# Sheet1.net
KiCad netlist of a schematic drawn in Altium Designer
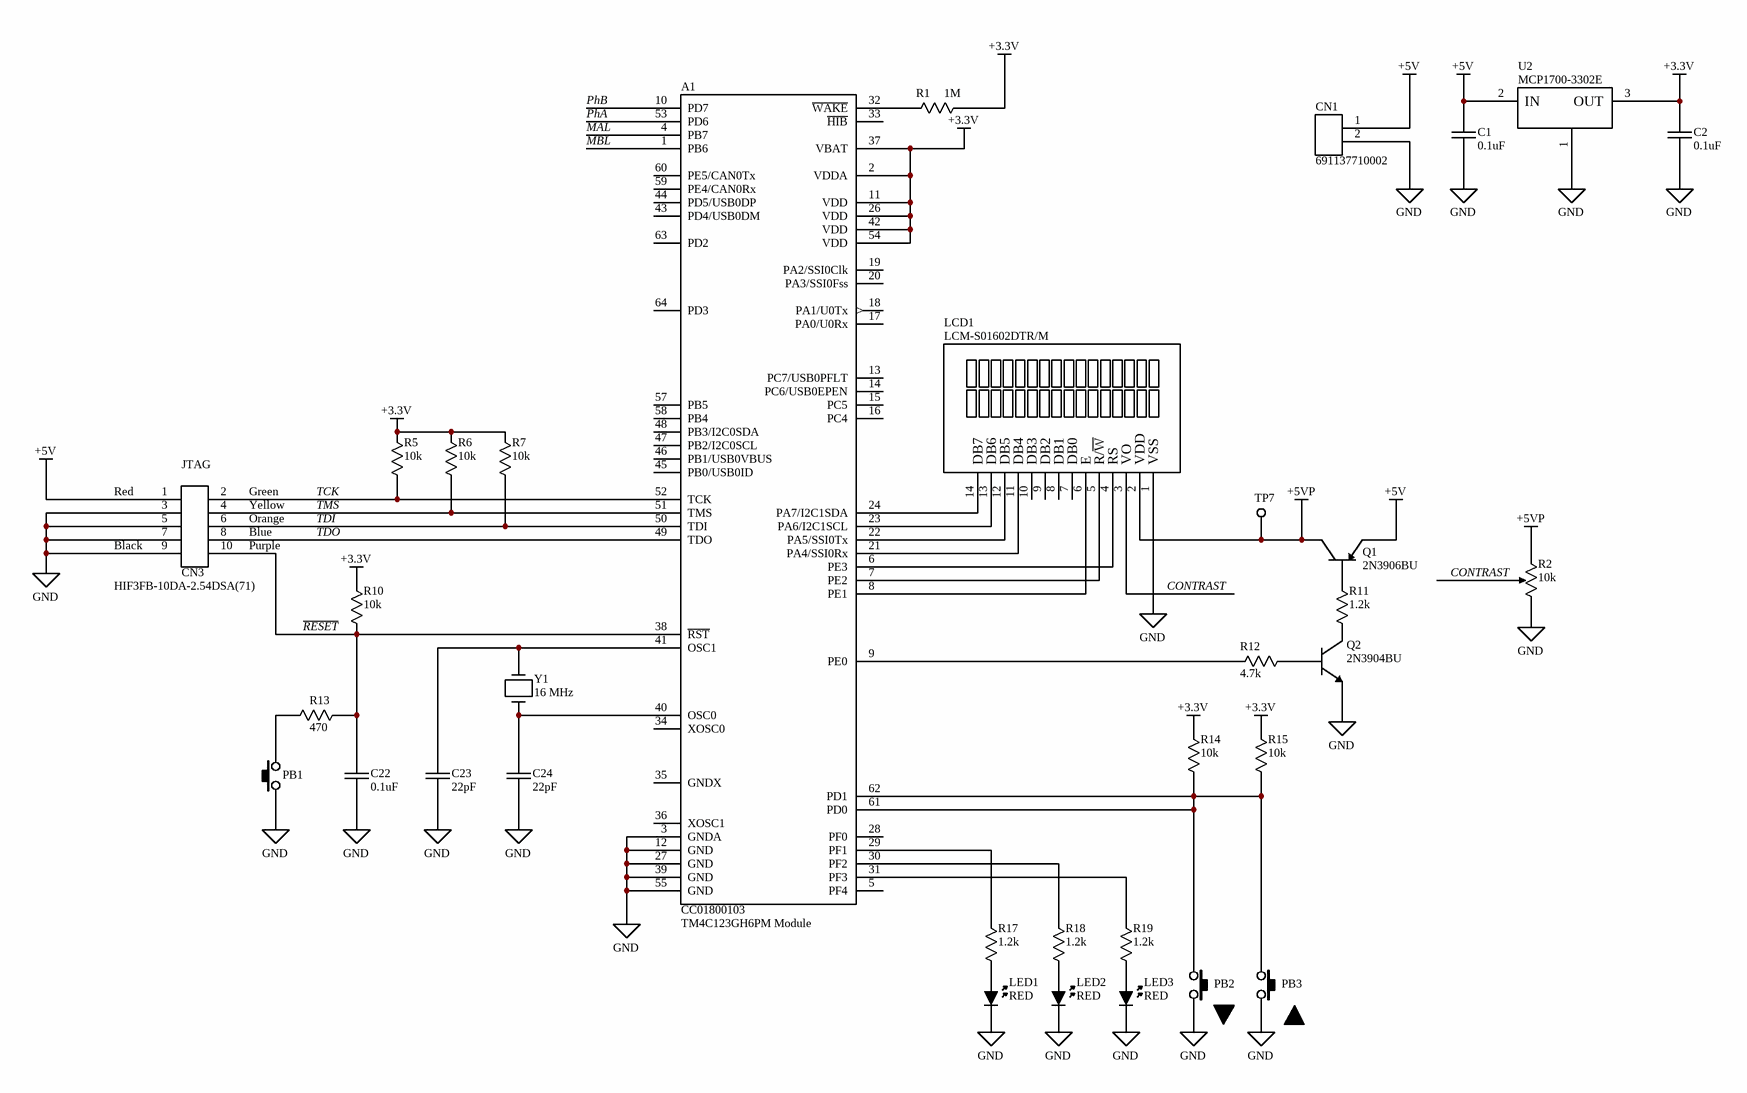
[diagram p0: Sheet1.SchDoc]

(export (version "E")
  (design (tool "Eeschema 10.0.6"))
  (components
    (comp (ref "A1")
      (value "CC01800103")
      (footprint "CC01800102")
      (description "Tiva TM4C123GH6PM Microcontroller Module")
      (fields
        (field (name "MANUFACTURER") "Confederation College")
        (field (name "MICROCONTROLLER") "TM4C123GH6PM Module")
      )
      (libsource (lib "Schlib1") (part "CC01800103"))
    )
    (comp (ref "C1")
      (value "0.1uF")
      (footprint "C320C104M5R5TA")
      (description "0.1 uF, 50 V Ceramic Capacitor")
      (fields (field (name "MANUFACTURER") "Kemet") (field (name "PARTNUMBER") "C320C104M5R5TA"))
      (libsource (lib "Schlib1") (part "C320C104M5R5TA"))
    )
    (comp (ref "C2")
      (value "0.1uF")
      (footprint "C320C104M5R5TA")
      (description "0.1 uF, 50 V Ceramic Capacitor")
      (fields (field (name "MANUFACTURER") "Kemet") (field (name "PARTNUMBER") "C320C104M5R5TA"))
      (libsource (lib "Schlib1") (part "C320C104M5R5TA"))
    )
    (comp (ref "C22")
      (value "0.1uF")
      (footprint "C320C104M5R5TA")
      (description "0.1 uF, 50 V Ceramic Capacitor")
      (fields (field (name "MANUFACTURER") "Kemet") (field (name "PARTNUMBER") "C320C104M5R5TA"))
      (libsource (lib "Schlib1") (part "C320C104M5R5TA"))
    )
    (comp (ref "C23")
      (value "22pF")
      (footprint "K220J15C0GF5TH5")
      (description "22 pF, 50 V Ceramic Capacitor")
      (fields (field (name "MANUFACTURER") "Vishay") (field (name "PARTNUMBER") "K220J15C0GF5TH5"))
      (libsource (lib "Schlib1") (part "K220J15C0GF5TH5"))
    )
    (comp (ref "C24")
      (value "22pF")
      (footprint "K220J15C0GF5TH5")
      (description "22 pF, 50 V Ceramic Capacitor")
      (fields (field (name "MANUFACTURER") "Vishay") (field (name "PARTNUMBER") "K220J15C0GF5TH5"))
      (libsource (lib "Schlib1") (part "K220J15C0GF5TH5"))
    )
    (comp (ref "CN1")
      (value "691137710002")
      (footprint "691137710002")
      (description "TERM BLK 2POS SIDE ENTRY 5MM PCB")
      (fields (field (name "MANUFACTURER") "Wurth Elektronk"))
      (libsource (lib "Schlib1") (part "691137710002"))
    )
    (comp (ref "CN3")
      (value "HIF3FB-10DA-2.54DSA(71)")
      (footprint "HIF3FB-10DA-2.54DSA(71)")
      (description "CONN RCPT 10POS 0.1 GOLD PCB")
      (fields (field (name "MANUFACTURER") "Hirose Electric Co, Ltd"))
      (libsource (lib "Schlib1") (part "HIF3FB-10DA-2.54DSA(71)"))
    )
    (comp (ref "LCD1")
      (value "LCM-S01602DTR/M")
      (footprint "LCM-S01602DTR/M")
      (description "16x2 Character LCD Module, TN, Reflective")
      (fields (field (name "MANUFACTURER") "Lumex, Inc."))
      (libsource (lib "Schlib1") (part "LCM-S01602DTR/M"))
    )
    (comp (ref "LED1")
      (value "RED")
      (footprint "C503B-RCN-CW0Z0AA1")
      (description "5 mm Red Round LED")
      (fields (field (name "MANUFACTURER") "Cree, Inc.") (field (name "PARTNUMBER") "C503B-RCN-CW0Z0AA1"))
      (libsource (lib "Schlib1") (part "C503B-RCN-CW0Z0AA1"))
    )
    (comp (ref "LED2")
      (value "RED")
      (footprint "C503B-RCN-CW0Z0AA1")
      (description "5 mm Red Round LED")
      (fields (field (name "MANUFACTURER") "Cree, Inc.") (field (name "PARTNUMBER") "C503B-RCN-CW0Z0AA1"))
      (libsource (lib "Schlib1") (part "C503B-RCN-CW0Z0AA1"))
    )
    (comp (ref "LED3")
      (value "RED")
      (footprint "C503B-RCN-CW0Z0AA1")
      (description "5 mm Red Round LED")
      (fields (field (name "MANUFACTURER") "Cree, Inc.") (field (name "PARTNUMBER") "C503B-RCN-CW0Z0AA1"))
      (libsource (lib "Schlib1") (part "C503B-RCN-CW0Z0AA1"))
    )
    (comp (ref "PB1")
      (value "3-1825910-5")
      (footprint "3-1825910-5")
      (description "SWITCH TACTILE SPST-NO 0.05A 24V")
      (fields (field (name "MANUFACTURER") "TE Connectivity ALCOSWITCH Switches"))
      (libsource (lib "") (part "3-1825910-5_1"))
    )
    (comp (ref "PB2")
      (value "3-1825910-5")
      (footprint "3-1825910-5")
      (description "SWITCH TACTILE SPST-NO 0.05A 24V")
      (fields (field (name "MANUFACTURER") "TE Connectivity ALCOSWITCH Switches"))
      (libsource (lib "Schlib1") (part "3-1825910-5"))
    )
    (comp (ref "PB3")
      (value "3-1825910-5")
      (footprint "3-1825910-5")
      (description "SWITCH TACTILE SPST-NO 0.05A 24V")
      (fields (field (name "MANUFACTURER") "TE Connectivity ALCOSWITCH Switches"))
      (libsource (lib "Schlib1") (part "3-1825910-5"))
    )
    (comp (ref "Q1")
      (value "2N3906BU")
      (footprint "2N3906BU")
      (description "PNP General Purpose Amplifier")
      (fields (field (name "MANUFACTURER") "Fairchild Semiconductor Corporation"))
      (libsource (lib "Schlib1") (part "2N3906BU"))
    )
    (comp (ref "Q2")
      (value "2N3904BU")
      (footprint "2N3904BU")
      (description "NPN General Purpose Amplifier")
      (fields (field (name "MANUFACTURER") "Fairchild Semiconductor Corporation"))
      (libsource (lib "Schlib1") (part "2N3904BU"))
    )
    (comp (ref "R1")
      (value "1M")
      (footprint "1/2WattResistor")
      (description "1 Mega Ohm, ±5%, 0.5W Thru-Hole Resistor")
      (fields (field (name "MANUFACTURER") "Generic") (field (name "PARTNUMBER") "RES1k2-500mW-THRU-HOLE"))
      (libsource (lib "Schlib1") (part "RES1M-500mW-THRU-HOLE"))
    )
    (comp (ref "R2")
      (value "10k")
      (footprint "T93YA103KT20")
      (description "10 k, 21-Turn Trimmer")
      (fields (field (name "MANUFACTURER") "Vishay Sfernice") (field (name "PARTNUMBER") "T93YA103KT20"))
      (libsource (lib "Schlib1") (part "T93YA103KT20"))
    )
    (comp (ref "R5")
      (value "10k")
      (footprint "1/2WattResistor")
      (description "10k, ±5%, 0.5W Thru-Hole Resistor")
      (fields (field (name "MANUFACTURER") "Generic") (field (name "PARTNUMBER") "RES10k-500mW-THRU-HOLE"))
      (libsource (lib "Schlib1") (part "RES10k-500mW-THRU-HOLE"))
    )
    (comp (ref "R6")
      (value "10k")
      (footprint "1/2WattResistor")
      (description "10k, ±5%, 0.5W Thru-Hole Resistor")
      (fields (field (name "MANUFACTURER") "Generic") (field (name "PARTNUMBER") "RES10k-500mW-THRU-HOLE"))
      (libsource (lib "Schlib1") (part "RES10k-500mW-THRU-HOLE"))
    )
    (comp (ref "R7")
      (value "10k")
      (footprint "1/2WattResistor")
      (description "10k, ±5%, 0.5W Thru-Hole Resistor")
      (fields (field (name "MANUFACTURER") "Generic") (field (name "PARTNUMBER") "RES10k-500mW-THRU-HOLE"))
      (libsource (lib "Schlib1") (part "RES10k-500mW-THRU-HOLE"))
    )
    (comp (ref "R10")
      (value "10k")
      (footprint "1/2WattResistor")
      (description "10k, ±5%, 0.5W Thru-Hole Resistor")
      (fields (field (name "MANUFACTURER") "Generic") (field (name "PARTNUMBER") "RES10k-500mW-THRU-HOLE"))
      (libsource (lib "Schlib1") (part "RES10k-500mW-THRU-HOLE"))
    )
    (comp (ref "R11")
      (value "1.2k")
      (footprint "1/2WattResistor")
      (description "1.2k, ±5%, 0.5W Thru-Hole Resistor")
      (fields (field (name "MANUFACTURER") "Generic") (field (name "PARTNUMBER") "RES1k2-500mW-THRU-HOLE"))
      (libsource (lib "Schlib1") (part "RES1k2-500mW-THRU-HOLE"))
    )
    (comp (ref "R12")
      (value "4.7k")
      (footprint "1/2WattResistor")
      (description "4.7 kOhm, ±5%, 0.5W Thru-Hole Resistor")
      (fields (field (name "MANUFACTURER") "Generic") (field (name "PARTNUMBER") "RES4k7-500mW-THRU-HOLE"))
      (libsource (lib "Schlib1") (part "RES4k7-500mW-THRU-HOLE"))
    )
    (comp (ref "R13")
      (value "470")
      (footprint "1/2WattResistor")
      (description "470 Ohm, ±5%, 0.5W Thru-Hole Resistor")
      (fields (field (name "MANUFACTURER") "Generic") (field (name "PARTNUMBER") "RES470-500mW-THRU-HOLE"))
      (libsource (lib "Schlib1") (part "RES470-500mW-THRU-HOLE"))
    )
    (comp (ref "R14")
      (value "10k")
      (footprint "1/2WattResistor")
      (description "10k, ±5%, 0.5W Thru-Hole Resistor")
      (fields (field (name "MANUFACTURER") "Generic") (field (name "PARTNUMBER") "RES10k-500mW-THRU-HOLE"))
      (libsource (lib "Schlib1") (part "RES10k-500mW-THRU-HOLE"))
    )
    (comp (ref "R15")
      (value "10k")
      (footprint "1/2WattResistor")
      (description "10k, ±5%, 0.5W Thru-Hole Resistor")
      (fields (field (name "MANUFACTURER") "Generic") (field (name "PARTNUMBER") "RES10k-500mW-THRU-HOLE"))
      (libsource (lib "Schlib1") (part "RES10k-500mW-THRU-HOLE"))
    )
    (comp (ref "R17")
      (value "1.2k")
      (footprint "1/2WattResistor")
      (description "1.2k, ±5%, 0.5W Thru-Hole Resistor")
      (fields (field (name "MANUFACTURER") "Generic") (field (name "PARTNUMBER") "RES1k2-500mW-THRU-HOLE"))
      (libsource (lib "Schlib1") (part "RES1k2-500mW-THRU-HOLE"))
    )
    (comp (ref "R18")
      (value "1.2k")
      (footprint "1/2WattResistor")
      (description "1.2k, ±5%, 0.5W Thru-Hole Resistor")
      (fields (field (name "MANUFACTURER") "Generic") (field (name "PARTNUMBER") "RES1k2-500mW-THRU-HOLE"))
      (libsource (lib "Schlib1") (part "RES1k2-500mW-THRU-HOLE"))
    )
    (comp (ref "R19")
      (value "1.2k")
      (footprint "1/2WattResistor")
      (description "1.2k, ±5%, 0.5W Thru-Hole Resistor")
      (fields (field (name "MANUFACTURER") "Generic") (field (name "PARTNUMBER") "RES1k2-500mW-THRU-HOLE"))
      (libsource (lib "Schlib1") (part "RES1k2-500mW-THRU-HOLE"))
    )
    (comp (ref "TP7")
      (value "TESTPOINT-2MM")
      (footprint "TESTPOINT-2MM")
      (description "Test Point 2MM diameter")
      (libsource (lib "Schlib1") (part "TESTPOINT-2MM"))
    )
    (comp (ref "U2")
      (value "MCP1700-3302E")
      (footprint "MCP1700-3302E/TO")
      (description "Low Quiescent Current LDO")
      (fields (field (name "MANUFACTURER") "Microchip Technology"))
      (libsource (lib "Schlib1") (part "MCP1700-3302E"))
    )
    (comp (ref "Y1")
      (value "16 MHz")
      (footprint "ABL-16.000MHZ-B2")
      (description "16 MHz AC/49US (AT49) Microprocessor Crystall")
      (fields
        (field (name "PARTNUMBER") "ABL-16.000MHZ-B2")
        (field (name "MANUFACTURER") "Abracon Corporation")
      )
      (libsource (lib "Schlib1") (part "ABL-16.000MHZ-B2"))
    )
  )
  (nets
    (net (code "1") (name "+3.3V") (class "Default")
      (node (ref "A1") (pin "11") (pinfunction "VDD_11") (pintype "power_in"))
      (node (ref "A1") (pin "2") (pinfunction "VDDA_2") (pintype "power_in"))
      (node (ref "A1") (pin "26") (pinfunction "VDD_26") (pintype "passive"))
      (node (ref "A1") (pin "37") (pinfunction "VBAT_37") (pintype "passive"))
      (node (ref "A1") (pin "42") (pinfunction "VDD_42") (pintype "passive"))
      (node (ref "A1") (pin "54") (pinfunction "VDD_54") (pintype "power_in"))
      (node (ref "C2") (pin "2") (pinfunction "2_2") (pintype "passive"))
      (node (ref "R1") (pin "2") (pinfunction "2_2") (pintype "passive"))
      (node (ref "R10") (pin "2") (pinfunction "2_2") (pintype "passive"))
      (node (ref "R14") (pin "2") (pinfunction "2_2") (pintype "passive"))
      (node (ref "R15") (pin "2") (pinfunction "2_2") (pintype "passive"))
      (node (ref "R5") (pin "2") (pinfunction "2_2") (pintype "passive"))
      (node (ref "R6") (pin "2") (pinfunction "2_2") (pintype "passive"))
      (node (ref "R7") (pin "2") (pinfunction "2_2") (pintype "passive"))
      (node (ref "U2") (pin "3") (pinfunction "OUT_3") (pintype "passive"))
    )
    (net (code "2") (name "+5V") (class "Default")
      (node (ref "C1") (pin "2") (pinfunction "2_2") (pintype "passive"))
      (node (ref "CN1") (pin "1") (pinfunction "1_1") (pintype "passive"))
      (node (ref "CN3") (pin "1") (pinfunction "1_1") (pintype "passive"))
      (node (ref "Q1") (pin "1") (pinfunction "E_1") (pintype "passive"))
      (node (ref "U2") (pin "2") (pinfunction "IN_2") (pintype "passive"))
    )
    (net (code "3") (name "+5VP") (class "Default")
      (node (ref "LCD1") (pin "2") (pinfunction "VDD_2") (pintype "passive"))
      (node (ref "Q1") (pin "3") (pinfunction "C_3") (pintype "passive"))
      (node (ref "R2") (pin "1") (pinfunction "1_1") (pintype "passive"))
      (node (ref "TP7") (pin "1") (pintype "passive"))
    )
    (net (code "4") (name "/CONTRAST") (class "Default")
      (node (ref "LCD1") (pin "3") (pinfunction "VO_3") (pintype "passive"))
      (node (ref "R2") (pin "2") (pinfunction "2_2") (pintype "passive"))
    )
    (net (code "5") (name "/MAL") (class "Default")
      (node (ref "A1") (pin "4") (pinfunction "PB7_4") (pintype "passive"))
    )
    (net (code "6") (name "/MBL") (class "Default")
      (node (ref "A1") (pin "1") (pinfunction "PB6_1") (pintype "passive"))
    )
    (net (code "7") (name "/PhA") (class "Default")
      (node (ref "A1") (pin "53") (pinfunction "PD6_53") (pintype "passive"))
    )
    (net (code "8") (name "/PhB") (class "Default")
      (node (ref "A1") (pin "10") (pinfunction "PD7_10") (pintype "passive"))
    )
    (net (code "9") (name "/TCK") (class "Default")
      (node (ref "A1") (pin "52") (pinfunction "TCK_52") (pintype "passive"))
      (node (ref "CN3") (pin "2") (pinfunction "2_2") (pintype "passive"))
      (node (ref "R5") (pin "1") (pinfunction "1_1") (pintype "passive"))
    )
    (net (code "10") (name "/TDI") (class "Default")
      (node (ref "A1") (pin "50") (pinfunction "TDI_50") (pintype "passive"))
      (node (ref "CN3") (pin "6") (pinfunction "6_6") (pintype "passive"))
      (node (ref "R7") (pin "1") (pinfunction "1_1") (pintype "passive"))
    )
    (net (code "11") (name "/TDO") (class "Default")
      (node (ref "A1") (pin "49") (pinfunction "TDO_49") (pintype "passive"))
      (node (ref "CN3") (pin "8") (pinfunction "8_8") (pintype "passive"))
    )
    (net (code "12") (name "/TMS") (class "Default")
      (node (ref "A1") (pin "51") (pinfunction "TMS_51") (pintype "passive"))
      (node (ref "CN3") (pin "4") (pinfunction "4_4") (pintype "passive"))
      (node (ref "R6") (pin "1") (pinfunction "1_1") (pintype "passive"))
    )
    (net (code "13") (name "/~{RESET}") (class "Default")
      (node (ref "A1") (pin "38") (pinfunction "~{RST}_38") (pintype "passive"))
      (node (ref "C22") (pin "1") (pinfunction "1_1") (pintype "passive"))
      (node (ref "CN3") (pin "10") (pinfunction "10_10") (pintype "passive"))
      (node (ref "R10") (pin "1") (pinfunction "1_1") (pintype "passive"))
      (node (ref "R13") (pin "2") (pinfunction "2_2") (pintype "passive"))
    )
    (net (code "14") (name "GND") (class "Default")
      (node (ref "A1") (pin "12") (pinfunction "GND_12") (pintype "power_in"))
      (node (ref "A1") (pin "27") (pinfunction "GND_27") (pintype "passive"))
      (node (ref "A1") (pin "3") (pinfunction "GNDA_3") (pintype "power_in"))
      (node (ref "A1") (pin "39") (pinfunction "GND_39") (pintype "power_in"))
      (node (ref "A1") (pin "55") (pinfunction "GND_55") (pintype "power_in"))
      (node (ref "C1") (pin "1") (pinfunction "1_1") (pintype "passive"))
      (node (ref "C2") (pin "1") (pinfunction "1_1") (pintype "passive"))
      (node (ref "C22") (pin "2") (pinfunction "2_2") (pintype "passive"))
      (node (ref "C23") (pin "2") (pinfunction "2_2") (pintype "passive"))
      (node (ref "C24") (pin "2") (pinfunction "2_2") (pintype "passive"))
      (node (ref "CN1") (pin "2") (pinfunction "2_2") (pintype "passive"))
      (node (ref "CN3") (pin "3") (pinfunction "3_3") (pintype "passive"))
      (node (ref "CN3") (pin "5") (pinfunction "5_5") (pintype "passive"))
      (node (ref "CN3") (pin "7") (pinfunction "7_7") (pintype "passive"))
      (node (ref "CN3") (pin "9") (pinfunction "9_9") (pintype "passive"))
      (node (ref "LCD1") (pin "1") (pinfunction "VSS_1") (pintype "passive"))
      (node (ref "LED1") (pin "K") (pinfunction "K_K") (pintype "passive"))
      (node (ref "LED2") (pin "K") (pinfunction "K_K") (pintype "passive"))
      (node (ref "LED3") (pin "K") (pinfunction "K_K") (pintype "passive"))
      (node (ref "PB1") (pin "1") (pinfunction "1_1") (pintype "passive"))
      (node (ref "PB2") (pin "2") (pinfunction "2_2") (pintype "passive"))
      (node (ref "PB3") (pin "2") (pinfunction "2_2") (pintype "passive"))
      (node (ref "Q2") (pin "1") (pinfunction "E_1") (pintype "passive"))
      (node (ref "R2") (pin "3") (pinfunction "3_3") (pintype "passive"))
      (node (ref "U2") (pin "1") (pinfunction "GND_1") (pintype "passive"))
    )
    (net (code "15") (name "Net-(A1-OSC0)") (class "Default")
      (node (ref "A1") (pin "40") (pinfunction "OSC0_40") (pintype "power_in"))
      (node (ref "C24") (pin "1") (pinfunction "1_1") (pintype "passive"))
      (node (ref "Y1") (pin "1") (pinfunction "1_1") (pintype "passive"))
    )
    (net (code "16") (name "Net-(A1-OSC1)") (class "Default")
      (node (ref "A1") (pin "41") (pinfunction "OSC1_41") (pintype "power_in"))
      (node (ref "C23") (pin "1") (pinfunction "1_1") (pintype "passive"))
      (node (ref "Y1") (pin "2") (pinfunction "2_2") (pintype "passive"))
    )
    (net (code "17") (name "Net-(A1-PA4{slash}SSI0Rx)") (class "Default")
      (node (ref "A1") (pin "21") (pinfunction "PA4/SSI0Rx_21") (pintype "passive"))
      (node (ref "LCD1") (pin "11") (pinfunction "DB4_11") (pintype "passive"))
    )
    (net (code "18") (name "Net-(A1-PA5{slash}SSI0Tx)") (class "Default")
      (node (ref "A1") (pin "22") (pinfunction "PA5/SSI0Tx_22") (pintype "passive"))
      (node (ref "LCD1") (pin "12") (pinfunction "DB5_12") (pintype "passive"))
    )
    (net (code "19") (name "Net-(A1-PA6{slash}I2C1SCL)") (class "Default")
      (node (ref "A1") (pin "23") (pinfunction "PA6/I2C1SCL_23") (pintype "passive"))
      (node (ref "LCD1") (pin "13") (pinfunction "DB6_13") (pintype "passive"))
    )
    (net (code "20") (name "Net-(A1-PA7{slash}I2C1SDA)") (class "Default")
      (node (ref "A1") (pin "24") (pinfunction "PA7/I2C1SDA_24") (pintype "passive"))
      (node (ref "LCD1") (pin "14") (pinfunction "DB7_14") (pintype "passive"))
    )
    (net (code "21") (name "Net-(A1-PD0)") (class "Default")
      (node (ref "A1") (pin "61") (pinfunction "PD0_61") (pintype "passive"))
      (node (ref "A1") (pin "62") (pinfunction "PD1_62") (pintype "passive"))
      (node (ref "PB2") (pin "1") (pinfunction "1_1") (pintype "passive"))
      (node (ref "PB3") (pin "1") (pinfunction "1_1") (pintype "passive"))
      (node (ref "R14") (pin "1") (pinfunction "1_1") (pintype "passive"))
      (node (ref "R15") (pin "1") (pinfunction "1_1") (pintype "passive"))
    )
    (net (code "22") (name "Net-(A1-PE0)") (class "Default")
      (node (ref "A1") (pin "9") (pinfunction "PE0_9") (pintype "passive"))
      (node (ref "R12") (pin "1") (pinfunction "1_1") (pintype "passive"))
    )
    (net (code "23") (name "Net-(A1-PE1)") (class "Default")
      (node (ref "A1") (pin "8") (pinfunction "PE1_8") (pintype "passive"))
      (node (ref "LCD1") (pin "6") (pinfunction "E_6") (pintype "passive"))
    )
    (net (code "24") (name "Net-(A1-PE2)") (class "Default")
      (node (ref "A1") (pin "7") (pinfunction "PE2_7") (pintype "passive"))
      (node (ref "LCD1") (pin "5") (pinfunction "R/~{W}_5") (pintype "passive"))
    )
    (net (code "25") (name "Net-(A1-PE3)") (class "Default")
      (node (ref "A1") (pin "6") (pinfunction "PE3_6") (pintype "passive"))
      (node (ref "LCD1") (pin "4") (pinfunction "RS_4") (pintype "passive"))
    )
    (net (code "26") (name "Net-(A1-PF1)") (class "Default")
      (node (ref "A1") (pin "29") (pinfunction "PF1_29") (pintype "passive"))
      (node (ref "R17") (pin "2") (pinfunction "2_2") (pintype "passive"))
    )
    (net (code "27") (name "Net-(A1-PF2)") (class "Default")
      (node (ref "A1") (pin "30") (pinfunction "PF2_30") (pintype "passive"))
      (node (ref "R18") (pin "2") (pinfunction "2_2") (pintype "passive"))
    )
    (net (code "28") (name "Net-(A1-PF3)") (class "Default")
      (node (ref "A1") (pin "31") (pinfunction "PF3_31") (pintype "passive"))
      (node (ref "R19") (pin "2") (pinfunction "2_2") (pintype "passive"))
    )
    (net (code "29") (name "Net-(A1-~{WAKE})") (class "Default")
      (node (ref "A1") (pin "32") (pinfunction "~{WAKE}_32") (pintype "passive"))
      (node (ref "R1") (pin "1") (pinfunction "1_1") (pintype "passive"))
    )
    (net (code "30") (name "Net-(LED1-PadA)") (class "Default")
      (node (ref "LED1") (pin "A") (pinfunction "A_A") (pintype "passive"))
      (node (ref "R17") (pin "1") (pinfunction "1_1") (pintype "passive"))
    )
    (net (code "31") (name "Net-(LED2-PadA)") (class "Default")
      (node (ref "LED2") (pin "A") (pinfunction "A_A") (pintype "passive"))
      (node (ref "R18") (pin "1") (pinfunction "1_1") (pintype "passive"))
    )
    (net (code "32") (name "Net-(LED3-PadA)") (class "Default")
      (node (ref "LED3") (pin "A") (pinfunction "A_A") (pintype "passive"))
      (node (ref "R19") (pin "1") (pinfunction "1_1") (pintype "passive"))
    )
    (net (code "33") (name "Net-(PB1-Pad2)") (class "Default")
      (node (ref "PB1") (pin "2") (pinfunction "2_2") (pintype "passive"))
      (node (ref "R13") (pin "1") (pinfunction "1_1") (pintype "passive"))
    )
    (net (code "34") (name "Net-(Q1-B)") (class "Default")
      (node (ref "Q1") (pin "2") (pinfunction "B_2") (pintype "passive"))
      (node (ref "R11") (pin "2") (pinfunction "2_2") (pintype "passive"))
    )
    (net (code "35") (name "Net-(Q2-B)") (class "Default")
      (node (ref "Q2") (pin "2") (pinfunction "B_2") (pintype "passive"))
      (node (ref "R12") (pin "2") (pinfunction "2_2") (pintype "passive"))
    )
    (net (code "36") (name "Net-(Q2-C)") (class "Default")
      (node (ref "Q2") (pin "3") (pinfunction "C_3") (pintype "passive"))
      (node (ref "R11") (pin "1") (pinfunction "1_1") (pintype "passive"))
    )
    (net (code "37") (name "unconnected-(A1-GNDX-Pad35)") (class "Default")
      (node (ref "A1") (pin "35") (pinfunction "GNDX_35") (pintype "power_in"))
    )
    (net (code "38") (name "unconnected-(A1-PA0{slash}U0Rx-Pad17)") (class "Default")
      (node (ref "A1") (pin "17") (pinfunction "PA0/U0Rx_17") (pintype "passive"))
    )
    (net (code "39") (name "unconnected-(A1-PA1{slash}U0Tx-Pad18)") (class "Default")
      (node (ref "A1") (pin "18") (pinfunction "PA1/U0Tx_18") (pintype "output"))
    )
    (net (code "40") (name "unconnected-(A1-PA2{slash}SSI0Clk-Pad19)") (class "Default")
      (node (ref "A1") (pin "19") (pinfunction "PA2/SSI0Clk_19") (pintype "passive"))
    )
    (net (code "41") (name "unconnected-(A1-PA3{slash}SSI0Fss-Pad20)") (class "Default")
      (node (ref "A1") (pin "20") (pinfunction "PA3/SSI0Fss_20") (pintype "passive"))
    )
    (net (code "42") (name "unconnected-(A1-PB0{slash}USB0ID-Pad45)") (class "Default")
      (node (ref "A1") (pin "45") (pinfunction "PB0/USB0ID_45") (pintype "passive"))
    )
    (net (code "43") (name "unconnected-(A1-PB1{slash}USB0VBUS-Pad46)") (class "Default")
      (node (ref "A1") (pin "46") (pinfunction "PB1/USB0VBUS_46") (pintype "passive"))
    )
    (net (code "44") (name "unconnected-(A1-PB2{slash}I2C0SCL-Pad47)") (class "Default")
      (node (ref "A1") (pin "47") (pinfunction "PB2/I2C0SCL_47") (pintype "passive"))
    )
    (net (code "45") (name "unconnected-(A1-PB3{slash}I2C0SDA-Pad48)") (class "Default")
      (node (ref "A1") (pin "48") (pinfunction "PB3/I2C0SDA_48") (pintype "passive"))
    )
    (net (code "46") (name "unconnected-(A1-PB4-Pad58)") (class "Default")
      (node (ref "A1") (pin "58") (pinfunction "PB4_58") (pintype "passive"))
    )
    (net (code "47") (name "unconnected-(A1-PB5-Pad57)") (class "Default")
      (node (ref "A1") (pin "57") (pinfunction "PB5_57") (pintype "passive"))
    )
    (net (code "48") (name "unconnected-(A1-PC4-Pad16)") (class "Default")
      (node (ref "A1") (pin "16") (pinfunction "PC4_16") (pintype "passive"))
    )
    (net (code "49") (name "unconnected-(A1-PC5-Pad15)") (class "Default")
      (node (ref "A1") (pin "15") (pinfunction "PC5_15") (pintype "passive"))
    )
    (net (code "50") (name "unconnected-(A1-PC6{slash}USB0EPEN-Pad14)") (class "Default")
      (node (ref "A1") (pin "14") (pinfunction "PC6/USB0EPEN_14") (pintype "passive"))
    )
    (net (code "51") (name "unconnected-(A1-PC7{slash}USB0PFLT-Pad13)") (class "Default")
      (node (ref "A1") (pin "13") (pinfunction "PC7/USB0PFLT_13") (pintype "passive"))
    )
    (net (code "52") (name "unconnected-(A1-PD2-Pad63)") (class "Default")
      (node (ref "A1") (pin "63") (pinfunction "PD2_63") (pintype "passive"))
    )
    (net (code "53") (name "unconnected-(A1-PD3-Pad64)") (class "Default")
      (node (ref "A1") (pin "64") (pinfunction "PD3_64") (pintype "passive"))
    )
    (net (code "54") (name "unconnected-(A1-PD4{slash}USB0DM-Pad43)") (class "Default")
      (node (ref "A1") (pin "43") (pinfunction "PD4/USB0DM_43") (pintype "passive"))
    )
    (net (code "55") (name "unconnected-(A1-PD5{slash}USB0DP-Pad44)") (class "Default")
      (node (ref "A1") (pin "44") (pinfunction "PD5/USB0DP_44") (pintype "passive"))
    )
    (net (code "56") (name "unconnected-(A1-PE4{slash}CAN0Rx-Pad59)") (class "Default")
      (node (ref "A1") (pin "59") (pinfunction "PE4/CAN0Rx_59") (pintype "passive"))
    )
    (net (code "57") (name "unconnected-(A1-PE5{slash}CAN0Tx-Pad60)") (class "Default")
      (node (ref "A1") (pin "60") (pinfunction "PE5/CAN0Tx_60") (pintype "passive"))
    )
    (net (code "58") (name "unconnected-(A1-PF0-Pad28)") (class "Default")
      (node (ref "A1") (pin "28") (pinfunction "PF0_28") (pintype "passive"))
    )
    (net (code "59") (name "unconnected-(A1-PF4-Pad5)") (class "Default")
      (node (ref "A1") (pin "5") (pinfunction "PF4_5") (pintype "passive"))
    )
    (net (code "60") (name "unconnected-(A1-XOSC0-Pad34)") (class "Default")
      (node (ref "A1") (pin "34") (pinfunction "XOSC0_34") (pintype "passive"))
    )
    (net (code "61") (name "unconnected-(A1-XOSC1-Pad36)") (class "Default")
      (node (ref "A1") (pin "36") (pinfunction "XOSC1_36") (pintype "passive"))
    )
    (net (code "62") (name "unconnected-(A1-~{HIB}-Pad33)") (class "Default")
      (node (ref "A1") (pin "33") (pinfunction "~{HIB}_33") (pintype "passive"))
    )
    (net (code "63") (name "unconnected-(LCD1-DB0-Pad7)") (class "Default")
      (node (ref "LCD1") (pin "7") (pinfunction "DB0_7") (pintype "passive"))
    )
    (net (code "64") (name "unconnected-(LCD1-DB1-Pad8)") (class "Default")
      (node (ref "LCD1") (pin "8") (pinfunction "DB1_8") (pintype "passive"))
    )
    (net (code "65") (name "unconnected-(LCD1-DB2-Pad9)") (class "Default")
      (node (ref "LCD1") (pin "9") (pinfunction "DB2_9") (pintype "passive"))
    )
    (net (code "66") (name "unconnected-(LCD1-DB3-Pad10)") (class "Default")
      (node (ref "LCD1") (pin "10") (pinfunction "DB3_10") (pintype "passive"))
    )
  )
)
